# Headlight_Right_Board.net
KiCad netlist of a schematic drawn in Altium Designer
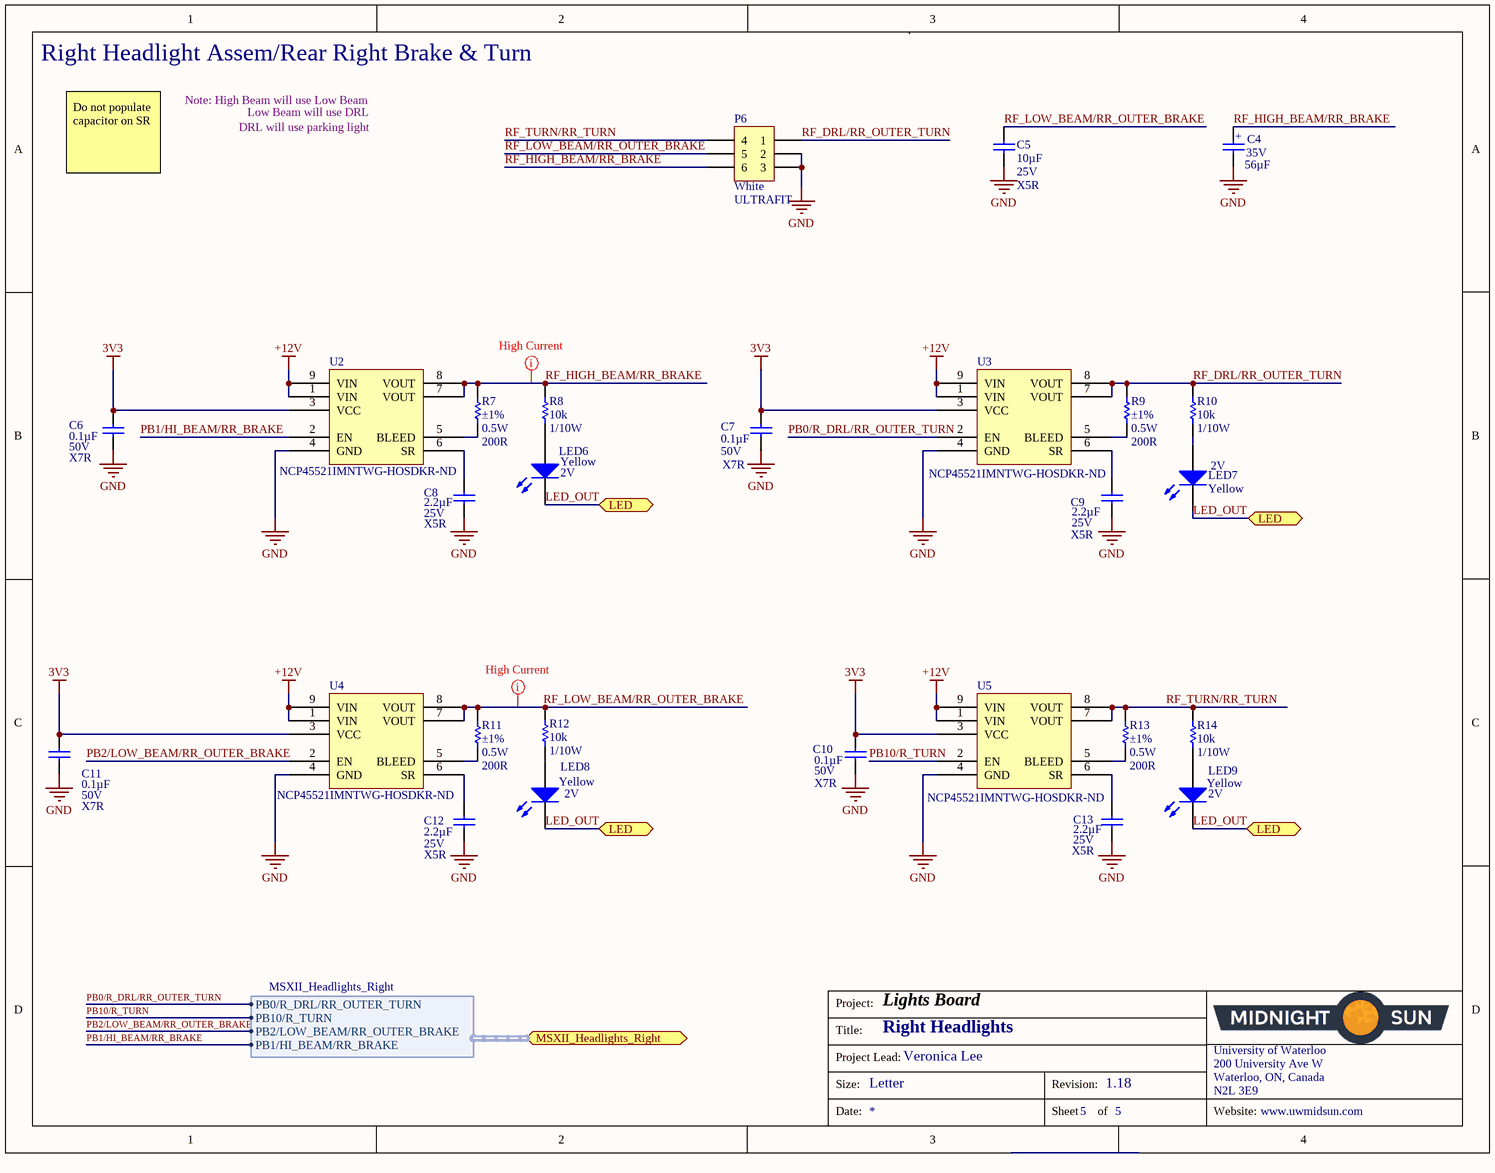
[diagram p0: Headlight_Right_Board.SchDoc]

(export (version "E")
  (design (tool "Eeschema 10.0.6"))
  (components
    (comp (ref "C4")
      (value "CAP ALUM 56UF 20% 35V RADIAL")
      (footprint "CAP ALUM 56UF 20% 35V RADIAL")
      (description "56µF 35V Aluminum Electrolytic Capacitors Radial, Can 1000 Hrs @ 105°C")
      (fields
        (field (name "MANUFACTURER") "Panasonic Electronic Components")
        (field (name "MANUFACTURER PART NUMBER") "EEU-FC1V560H")
        (field (name "VOLTAGE") "35V")
        (field (name "CAPACITANCE") "56µF")
      )
      (libsource (lib "Schematic Diagrams") (part "CAP ALUM 56UF 20% 35V RADIAL"))
    )
    (comp (ref "C5")
      (value "CAP CER 10uF 25V 20% X5R 0603")
      (footprint "CAP, 0603")
      (description "10µF ±20% 25V Ceramic Capacitor X5R 0603 (1608 Metric)")
      (fields
        (field (name "TOLERANCE") "±20%")
        (field (name "CAPACITANCE") "10µF")
        (field (name "VOLTAGE") "25V")
        (field (name "TEMPERATURE COEFFICIENT") "X5R")
      )
      (libsource (lib "Schematic Diagrams") (part "CAP CER 10uF 25V 20% X5R 0603"))
    )
    (comp (ref "C6")
      (value "CAP CER 0.1UF 50V 10% X7R 0603")
      (footprint "CAP, 0603")
      (description "0.10µF ±10% 50V Ceramic Capacitor X7R 0603 (1608 Metric)")
      (fields
        (field (name "TOLERANCE") "±10%")
        (field (name "CAPACITANCE") "0.1µF")
        (field (name "VOLTAGE") "50V")
        (field (name "TEMPERATURE COEFFICIENT") "X7R")
      )
      (libsource (lib "Schematic Diagrams") (part "CAP CER 0.1UF 50V 10% X7R 0603"))
    )
    (comp (ref "C7")
      (value "CAP CER 0.1UF 50V 10% X7R 0603")
      (footprint "CAP, 0603")
      (description "0.10µF ±10% 50V Ceramic Capacitor X7R 0603 (1608 Metric)")
      (fields
        (field (name "TOLERANCE") "±10%")
        (field (name "CAPACITANCE") "0.1µF")
        (field (name "VOLTAGE") "50V")
        (field (name "TEMPERATURE COEFFICIENT") "X7R")
      )
      (libsource (lib "Schematic Diagrams") (part "CAP CER 0.1UF 50V 10% X7R 0603"))
    )
    (comp (ref "C8")
      (value "CAP CER 2.2UF 25V 10% X5R 0603")
      (footprint "CAP, 0603")
      (description "2.2µF ±10% 25V Ceramic Capacitor X5R 0603 (1608 Metric)")
      (fields
        (field (name "TOLERANCE") "±10%")
        (field (name "CAPACITANCE") "2.2µF")
        (field (name "VOLTAGE") "25V")
        (field (name "TEMPERATURE COEFFICIENT") "X5R")
      )
      (libsource (lib "Schematic Diagrams") (part "CAP CER 2.2UF 25V 10% X5R 0603"))
    )
    (comp (ref "C9")
      (value "CAP CER 2.2UF 25V 10% X5R 0603")
      (footprint "CAP, 0603")
      (description "2.2µF ±10% 25V Ceramic Capacitor X5R 0603 (1608 Metric)")
      (fields
        (field (name "TOLERANCE") "±10%")
        (field (name "CAPACITANCE") "2.2µF")
        (field (name "VOLTAGE") "25V")
        (field (name "TEMPERATURE COEFFICIENT") "X5R")
      )
      (libsource (lib "Schematic Diagrams") (part "CAP CER 2.2UF 25V 10% X5R 0603"))
    )
    (comp (ref "C10")
      (value "CAP CER 0.1UF 50V 10% X7R 0603")
      (footprint "CAP, 0603")
      (description "0.10µF ±10% 50V Ceramic Capacitor X7R 0603 (1608 Metric)")
      (fields
        (field (name "TOLERANCE") "±10%")
        (field (name "CAPACITANCE") "0.1µF")
        (field (name "VOLTAGE") "50V")
        (field (name "TEMPERATURE COEFFICIENT") "X7R")
      )
      (libsource (lib "Schematic Diagrams") (part "CAP CER 0.1UF 50V 10% X7R 0603"))
    )
    (comp (ref "C11")
      (value "CAP CER 0.1UF 50V 10% X7R 0603")
      (footprint "CAP, 0603")
      (description "0.10µF ±10% 50V Ceramic Capacitor X7R 0603 (1608 Metric)")
      (fields
        (field (name "TOLERANCE") "±10%")
        (field (name "CAPACITANCE") "0.1µF")
        (field (name "VOLTAGE") "50V")
        (field (name "TEMPERATURE COEFFICIENT") "X7R")
      )
      (libsource (lib "Schematic Diagrams") (part "CAP CER 0.1UF 50V 10% X7R 0603"))
    )
    (comp (ref "C12")
      (value "CAP CER 2.2UF 25V 10% X5R 0603")
      (footprint "CAP, 0603")
      (description "2.2µF ±10% 25V Ceramic Capacitor X5R 0603 (1608 Metric)")
      (fields
        (field (name "TOLERANCE") "±10%")
        (field (name "CAPACITANCE") "2.2µF")
        (field (name "VOLTAGE") "25V")
        (field (name "TEMPERATURE COEFFICIENT") "X5R")
      )
      (libsource (lib "Schematic Diagrams") (part "CAP CER 2.2UF 25V 10% X5R 0603"))
    )
    (comp (ref "C13")
      (value "CAP CER 2.2UF 25V 10% X5R 0603")
      (footprint "CAP, 0603")
      (description "2.2µF ±10% 25V Ceramic Capacitor X5R 0603 (1608 Metric)")
      (fields
        (field (name "TOLERANCE") "±10%")
        (field (name "CAPACITANCE") "2.2µF")
        (field (name "VOLTAGE") "25V")
        (field (name "TEMPERATURE COEFFICIENT") "X5R")
      )
      (libsource (lib "Schematic Diagrams") (part "CAP CER 2.2UF 25V 10% X5R 0603"))
    )
    (comp (ref "LED6")
      (value "LED YELLOW CLEAR 2.1V 0603")
      (footprint "LED_0603")
      (description "Yellow 590nm LED Indication - Discrete 2V 0603 (1608 Metric)")
      (fields
        (field (name "MANUFACTURER") "Wurth Electronics Inc.")
        (field (name "MANUFACTURER PART NUMBER") "150060YS75000")
        (field (name "COLOR") "Yellow")
        (field (name "VOLTAGE - FORWARD (VF) (TYP)") "2V")
      )
      (libsource (lib "Schematic Diagrams") (part "LED YELLOW CLEAR 2.1V 0603"))
    )
    (comp (ref "LED7")
      (value "LED YELLOW CLEAR 2.1V 0603")
      (footprint "LED_0603")
      (description "Yellow 590nm LED Indication - Discrete 2V 0603 (1608 Metric)")
      (fields
        (field (name "MANUFACTURER") "Wurth Electronics Inc.")
        (field (name "MANUFACTURER PART NUMBER") "150060YS75000")
        (field (name "COLOR") "Yellow")
        (field (name "VOLTAGE - FORWARD (VF) (TYP)") "2V")
      )
      (libsource (lib "Schematic Diagrams") (part "LED YELLOW CLEAR 2.1V 0603"))
    )
    (comp (ref "LED8")
      (value "LED YELLOW CLEAR 2.1V 0603")
      (footprint "LED_0603")
      (description "Yellow 590nm LED Indication - Discrete 2V 0603 (1608 Metric)")
      (fields
        (field (name "MANUFACTURER") "Wurth Electronics Inc.")
        (field (name "MANUFACTURER PART NUMBER") "150060YS75000")
        (field (name "COLOR") "Yellow")
        (field (name "VOLTAGE - FORWARD (VF) (TYP)") "2V")
      )
      (libsource (lib "Schematic Diagrams") (part "LED YELLOW CLEAR 2.1V 0603"))
    )
    (comp (ref "LED9")
      (value "LED YELLOW CLEAR 2.1V 0603")
      (footprint "LED_0603")
      (description "Yellow 590nm LED Indication - Discrete 2V 0603 (1608 Metric)")
      (fields
        (field (name "MANUFACTURER") "Wurth Electronics Inc.")
        (field (name "MANUFACTURER PART NUMBER") "150060YS75000")
        (field (name "COLOR") "Yellow")
        (field (name "VOLTAGE - FORWARD (VF) (TYP)") "2V")
      )
      (libsource (lib "Schematic Diagrams") (part "LED YELLOW CLEAR 2.1V 0603"))
    )
    (comp (ref "P6")
      (value "CONN 6POS ULTRA-FIT NATURAL COLOR 0.138\"")
      (footprint "CONN, 6POS ULTRA-FIT - NATURAL COLOR")
      (description "6 Positions Header Connector 0.138\" (3.50mm) Through Hole Tin")
      (fields (field (name "INSULATION COLOR") "White") (field (name "SERIES") "ULTRAFIT"))
      (libsource (lib "Schematic Diagrams") (part "CONN 6POS ULTRA-FIT NATURAL COLOR 0.138{dblquote}"))
    )
    (comp (ref "R7")
      (value "200R")
      (footprint "RES 0805")
      (fields
        (field (name "MANUFACTURER") "Panasonic Electronic Components")
        (field (name "MANUFACTURER PART NUMBER") "ERJ-P06F2000V")
        (field (name "TOLERANCE") "±1%")
        (field (name "POWER (WATTS)") "0.5W")
        (field (name "Comment") "RES SMD 200 OHM 1% 1/2W 0805")
      )
      (libsource (lib "Schematic Diagrams") (part "RES SMD 200 OHM 1% 1/2W 0805"))
    )
    (comp (ref "R8")
      (value "RES 10K OHM 1% 1/10W 0603")
      (footprint "RES, 0603")
      (description "RES SMD 10K OHM 1% 1/10W 0603")
      (fields
        (field (name "TOLERANCE") "±1%")
        (field (name "RESISTANCE") "10k")
        (field (name "POWER") "1/10W")
      )
      (libsource (lib "Schematic Diagrams") (part "RES 10K OHM 1% 1/10W 0603"))
    )
    (comp (ref "R9")
      (value "200R")
      (footprint "RES 0805")
      (fields
        (field (name "MANUFACTURER") "Panasonic Electronic Components")
        (field (name "MANUFACTURER PART NUMBER") "ERJ-P06F2000V")
        (field (name "TOLERANCE") "±1%")
        (field (name "POWER (WATTS)") "0.5W")
        (field (name "Comment") "RES SMD 200 OHM 1% 1/2W 0805")
      )
      (libsource (lib "Schematic Diagrams") (part "RES SMD 200 OHM 1% 1/2W 0805"))
    )
    (comp (ref "R10")
      (value "RES 10K OHM 1% 1/10W 0603")
      (footprint "RES, 0603")
      (description "RES SMD 10K OHM 1% 1/10W 0603")
      (fields
        (field (name "TOLERANCE") "±1%")
        (field (name "RESISTANCE") "10k")
        (field (name "POWER") "1/10W")
      )
      (libsource (lib "Schematic Diagrams") (part "RES 10K OHM 1% 1/10W 0603"))
    )
    (comp (ref "R11")
      (value "200R")
      (footprint "RES 0805")
      (fields
        (field (name "MANUFACTURER") "Panasonic Electronic Components")
        (field (name "MANUFACTURER PART NUMBER") "ERJ-P06F2000V")
        (field (name "TOLERANCE") "±1%")
        (field (name "POWER (WATTS)") "0.5W")
        (field (name "Comment") "RES SMD 200 OHM 1% 1/2W 0805")
      )
      (libsource (lib "Schematic Diagrams") (part "RES SMD 200 OHM 1% 1/2W 0805"))
    )
    (comp (ref "R12")
      (value "RES 10K OHM 1% 1/10W 0603")
      (footprint "RES, 0603")
      (description "RES SMD 10K OHM 1% 1/10W 0603")
      (fields
        (field (name "TOLERANCE") "±1%")
        (field (name "RESISTANCE") "10k")
        (field (name "POWER") "1/10W")
      )
      (libsource (lib "Schematic Diagrams") (part "RES 10K OHM 1% 1/10W 0603"))
    )
    (comp (ref "R13")
      (value "200R")
      (footprint "RES 0805")
      (fields
        (field (name "MANUFACTURER") "Panasonic Electronic Components")
        (field (name "MANUFACTURER PART NUMBER") "ERJ-P06F2000V")
        (field (name "TOLERANCE") "±1%")
        (field (name "POWER (WATTS)") "0.5W")
        (field (name "Comment") "RES SMD 200 OHM 1% 1/2W 0805")
      )
      (libsource (lib "Schematic Diagrams") (part "RES SMD 200 OHM 1% 1/2W 0805"))
    )
    (comp (ref "R14")
      (value "RES 10K OHM 1% 1/10W 0603")
      (footprint "RES, 0603")
      (description "RES SMD 10K OHM 1% 1/10W 0603")
      (fields
        (field (name "TOLERANCE") "±1%")
        (field (name "RESISTANCE") "10k")
        (field (name "POWER") "1/10W")
      )
      (libsource (lib "Schematic Diagrams") (part "RES 10K OHM 1% 1/10W 0603"))
    )
    (comp (ref "U2")
      (value "IC LOAD SWITCH ACT-HI 10.5A 8DFN")
      (footprint "IC LOAD SWITCH ACT-HI 10.5A 8DFN")
      (description "NCP45521IMNTWG-H")
      (fields
        (field (name "MANUFACTURER") "ON Semiconductor")
        (field (name "SUPPLIER PART NUMBER 2") "NCP45521IMNTWG-HOSDKR-ND")
      )
      (libsource (lib "Schematic Diagrams") (part "IC LOAD SWITCH ACT-HI 10.5A 8DFN"))
    )
    (comp (ref "U3")
      (value "IC LOAD SWITCH ACT-HI 10.5A 8DFN")
      (footprint "IC LOAD SWITCH ACT-HI 10.5A 8DFN")
      (description "NCP45521IMNTWG-H")
      (fields
        (field (name "MANUFACTURER") "ON Semiconductor")
        (field (name "SUPPLIER PART NUMBER 2") "NCP45521IMNTWG-HOSDKR-ND")
      )
      (libsource (lib "Schematic Diagrams") (part "IC LOAD SWITCH ACT-HI 10.5A 8DFN"))
    )
    (comp (ref "U4")
      (value "IC LOAD SWITCH ACT-HI 10.5A 8DFN")
      (footprint "IC LOAD SWITCH ACT-HI 10.5A 8DFN")
      (description "NCP45521IMNTWG-H")
      (fields
        (field (name "MANUFACTURER") "ON Semiconductor")
        (field (name "SUPPLIER PART NUMBER 2") "NCP45521IMNTWG-HOSDKR-ND")
      )
      (libsource (lib "Schematic Diagrams") (part "IC LOAD SWITCH ACT-HI 10.5A 8DFN"))
    )
    (comp (ref "U5")
      (value "IC LOAD SWITCH ACT-HI 10.5A 8DFN")
      (footprint "IC LOAD SWITCH ACT-HI 10.5A 8DFN")
      (description "NCP45521IMNTWG-H")
      (fields
        (field (name "MANUFACTURER") "ON Semiconductor")
        (field (name "SUPPLIER PART NUMBER 2") "NCP45521IMNTWG-HOSDKR-ND")
      )
      (libsource (lib "Schematic Diagrams") (part "IC LOAD SWITCH ACT-HI 10.5A 8DFN"))
    )
  )
  (nets
    (net (code "2") (name "+12V") (class "Default")
      (node (ref "U2") (pin "1") (pinfunction "VIN_1") (pintype "passive"))
      (node (ref "U2") (pin "9") (pinfunction "VIN_9") (pintype "passive"))
      (node (ref "U3") (pin "1") (pinfunction "VIN_1") (pintype "passive"))
      (node (ref "U3") (pin "9") (pinfunction "VIN_9") (pintype "passive"))
      (node (ref "U4") (pin "1") (pinfunction "VIN_1") (pintype "passive"))
      (node (ref "U4") (pin "9") (pinfunction "VIN_9") (pintype "passive"))
      (node (ref "U5") (pin "1") (pinfunction "VIN_1") (pintype "passive"))
      (node (ref "U5") (pin "9") (pinfunction "VIN_9") (pintype "passive"))
    )
    (net (code "3") (name "/LED_OUT") (class "Default")
      (node (ref "LED6") (pin "2") (pinfunction "K_2") (pintype "passive"))
      (node (ref "LED7") (pin "2") (pinfunction "K_2") (pintype "passive"))
      (node (ref "LED8") (pin "2") (pinfunction "K_2") (pintype "passive"))
      (node (ref "LED9") (pin "2") (pinfunction "K_2") (pintype "passive"))
    )
    (net (code "4") (name "/PB0{slash}R_DRL{slash}RR_OUTER_TURN") (class "Default")
      (node (ref "U3") (pin "2") (pinfunction "EN_2") (pintype "passive"))
    )
    (net (code "5") (name "/PB1{slash}HI_BEAM{slash}RR_BRAKE") (class "Default")
      (node (ref "U2") (pin "2") (pinfunction "EN_2") (pintype "passive"))
    )
    (net (code "6") (name "/PB2{slash}LOW_BEAM{slash}RR_OUTER_BRAKE") (class "Default")
      (node (ref "U4") (pin "2") (pinfunction "EN_2") (pintype "passive"))
    )
    (net (code "7") (name "/PB10{slash}R_TURN") (class "Default")
      (node (ref "U5") (pin "2") (pinfunction "EN_2") (pintype "passive"))
    )
    (net (code "8") (name "/RF_DRL{slash}RR_OUTER_TURN") (class "Default")
      (node (ref "P6") (pin "1") (pinfunction "1_1") (pintype "passive"))
      (node (ref "R10") (pin "1") (pinfunction "1_1") (pintype "passive"))
      (node (ref "R9") (pin "1") (pinfunction "1_1") (pintype "passive"))
      (node (ref "U3") (pin "7") (pinfunction "VOUT_7") (pintype "passive"))
      (node (ref "U3") (pin "8") (pinfunction "VOUT_8") (pintype "passive"))
    )
    (net (code "9") (name "/RF_HIGH_BEAM{slash}RR_BRAKE") (class "Default")
      (node (ref "C4") (pin "1") (pinfunction "1_1") (pintype "passive"))
      (node (ref "P6") (pin "6") (pinfunction "6_6") (pintype "passive"))
      (node (ref "R7") (pin "2") (pinfunction "2_2") (pintype "passive"))
      (node (ref "R8") (pin "1") (pinfunction "1_1") (pintype "passive"))
      (node (ref "U2") (pin "7") (pinfunction "VOUT_7") (pintype "passive"))
      (node (ref "U2") (pin "8") (pinfunction "VOUT_8") (pintype "passive"))
    )
    (net (code "10") (name "/RF_LOW_BEAM{slash}RR_OUTER_BRAKE") (class "Default")
      (node (ref "C5") (pin "2") (pinfunction "2_2") (pintype "passive"))
      (node (ref "P6") (pin "5") (pinfunction "5_5") (pintype "passive"))
      (node (ref "R11") (pin "1") (pinfunction "1_1") (pintype "passive"))
      (node (ref "R12") (pin "1") (pinfunction "1_1") (pintype "passive"))
      (node (ref "U4") (pin "7") (pinfunction "VOUT_7") (pintype "passive"))
      (node (ref "U4") (pin "8") (pinfunction "VOUT_8") (pintype "passive"))
    )
    (net (code "11") (name "/RF_TURN{slash}RR_TURN") (class "Default")
      (node (ref "P6") (pin "4") (pinfunction "4_4") (pintype "passive"))
      (node (ref "R13") (pin "1") (pinfunction "1_1") (pintype "passive"))
      (node (ref "R14") (pin "1") (pinfunction "1_1") (pintype "passive"))
      (node (ref "U5") (pin "7") (pinfunction "VOUT_7") (pintype "passive"))
      (node (ref "U5") (pin "8") (pinfunction "VOUT_8") (pintype "passive"))
    )
    (net (code "13") (name "3V3") (class "Default")
      (node (ref "C10") (pin "1") (pinfunction "1_1") (pintype "passive"))
      (node (ref "C11") (pin "1") (pinfunction "1_1") (pintype "passive"))
      (node (ref "C6") (pin "1") (pinfunction "1_1") (pintype "passive"))
      (node (ref "C7") (pin "1") (pinfunction "1_1") (pintype "passive"))
      (node (ref "U2") (pin "3") (pinfunction "VCC_3") (pintype "passive"))
      (node (ref "U3") (pin "3") (pinfunction "VCC_3") (pintype "passive"))
      (node (ref "U4") (pin "3") (pinfunction "VCC_3") (pintype "passive"))
      (node (ref "U5") (pin "3") (pinfunction "VCC_3") (pintype "passive"))
    )
    (net (code "14") (name "GND") (class "Default")
      (node (ref "C10") (pin "2") (pinfunction "2_2") (pintype "passive"))
      (node (ref "C11") (pin "2") (pinfunction "2_2") (pintype "passive"))
      (node (ref "C12") (pin "2") (pinfunction "2_2") (pintype "passive"))
      (node (ref "C13") (pin "2") (pinfunction "2_2") (pintype "passive"))
      (node (ref "C4") (pin "2") (pinfunction "2_2") (pintype "passive"))
      (node (ref "C5") (pin "1") (pinfunction "1_1") (pintype "passive"))
      (node (ref "C6") (pin "2") (pinfunction "2_2") (pintype "passive"))
      (node (ref "C7") (pin "2") (pinfunction "2_2") (pintype "passive"))
      (node (ref "C8") (pin "2") (pinfunction "2_2") (pintype "passive"))
      (node (ref "C9") (pin "2") (pinfunction "2_2") (pintype "passive"))
      (node (ref "P6") (pin "2") (pinfunction "2_2") (pintype "passive"))
      (node (ref "P6") (pin "3") (pinfunction "3_3") (pintype "passive"))
      (node (ref "U2") (pin "4") (pinfunction "GND_4") (pintype "passive"))
      (node (ref "U3") (pin "4") (pinfunction "GND_4") (pintype "passive"))
      (node (ref "U4") (pin "4") (pinfunction "GND_4") (pintype "passive"))
      (node (ref "U5") (pin "4") (pinfunction "GND_4") (pintype "passive"))
    )
    (net (code "15") (name "Net-(LED6-A)") (class "Default")
      (node (ref "LED6") (pin "1") (pinfunction "A_1") (pintype "passive"))
      (node (ref "R8") (pin "2") (pinfunction "2_2") (pintype "passive"))
    )
    (net (code "16") (name "Net-(LED7-A)") (class "Default")
      (node (ref "LED7") (pin "1") (pinfunction "A_1") (pintype "passive"))
      (node (ref "R10") (pin "2") (pinfunction "2_2") (pintype "passive"))
    )
    (net (code "17") (name "Net-(LED8-A)") (class "Default")
      (node (ref "LED8") (pin "1") (pinfunction "A_1") (pintype "passive"))
      (node (ref "R12") (pin "2") (pinfunction "2_2") (pintype "passive"))
    )
    (net (code "18") (name "Net-(LED9-A)") (class "Default")
      (node (ref "LED9") (pin "1") (pinfunction "A_1") (pintype "passive"))
      (node (ref "R14") (pin "2") (pinfunction "2_2") (pintype "passive"))
    )
    (net (code "19") (name "Net-(U2-BLEED)") (class "Default")
      (node (ref "R7") (pin "1") (pinfunction "1_1") (pintype "passive"))
      (node (ref "U2") (pin "5") (pinfunction "BLEED_5") (pintype "passive"))
    )
    (net (code "20") (name "Net-(U2-SR)") (class "Default")
      (node (ref "C8") (pin "1") (pinfunction "1_1") (pintype "passive"))
      (node (ref "U2") (pin "6") (pinfunction "SR_6") (pintype "passive"))
    )
    (net (code "21") (name "Net-(U3-BLEED)") (class "Default")
      (node (ref "R9") (pin "2") (pinfunction "2_2") (pintype "passive"))
      (node (ref "U3") (pin "5") (pinfunction "BLEED_5") (pintype "passive"))
    )
    (net (code "22") (name "Net-(U3-SR)") (class "Default")
      (node (ref "C9") (pin "1") (pinfunction "1_1") (pintype "passive"))
      (node (ref "U3") (pin "6") (pinfunction "SR_6") (pintype "passive"))
    )
    (net (code "23") (name "Net-(U4-BLEED)") (class "Default")
      (node (ref "R11") (pin "2") (pinfunction "2_2") (pintype "passive"))
      (node (ref "U4") (pin "5") (pinfunction "BLEED_5") (pintype "passive"))
    )
    (net (code "24") (name "Net-(U4-SR)") (class "Default")
      (node (ref "C12") (pin "1") (pinfunction "1_1") (pintype "passive"))
      (node (ref "U4") (pin "6") (pinfunction "SR_6") (pintype "passive"))
    )
    (net (code "25") (name "Net-(U5-BLEED)") (class "Default")
      (node (ref "R13") (pin "2") (pinfunction "2_2") (pintype "passive"))
      (node (ref "U5") (pin "5") (pinfunction "BLEED_5") (pintype "passive"))
    )
    (net (code "26") (name "Net-(U5-SR)") (class "Default")
      (node (ref "C13") (pin "1") (pinfunction "1_1") (pintype "passive"))
      (node (ref "U5") (pin "6") (pinfunction "SR_6") (pintype "passive"))
    )
  )
)
